# AVR128DB48_Curiosity_Nano_Debugger.net
KiCad netlist of a schematic drawn in Altium Designer
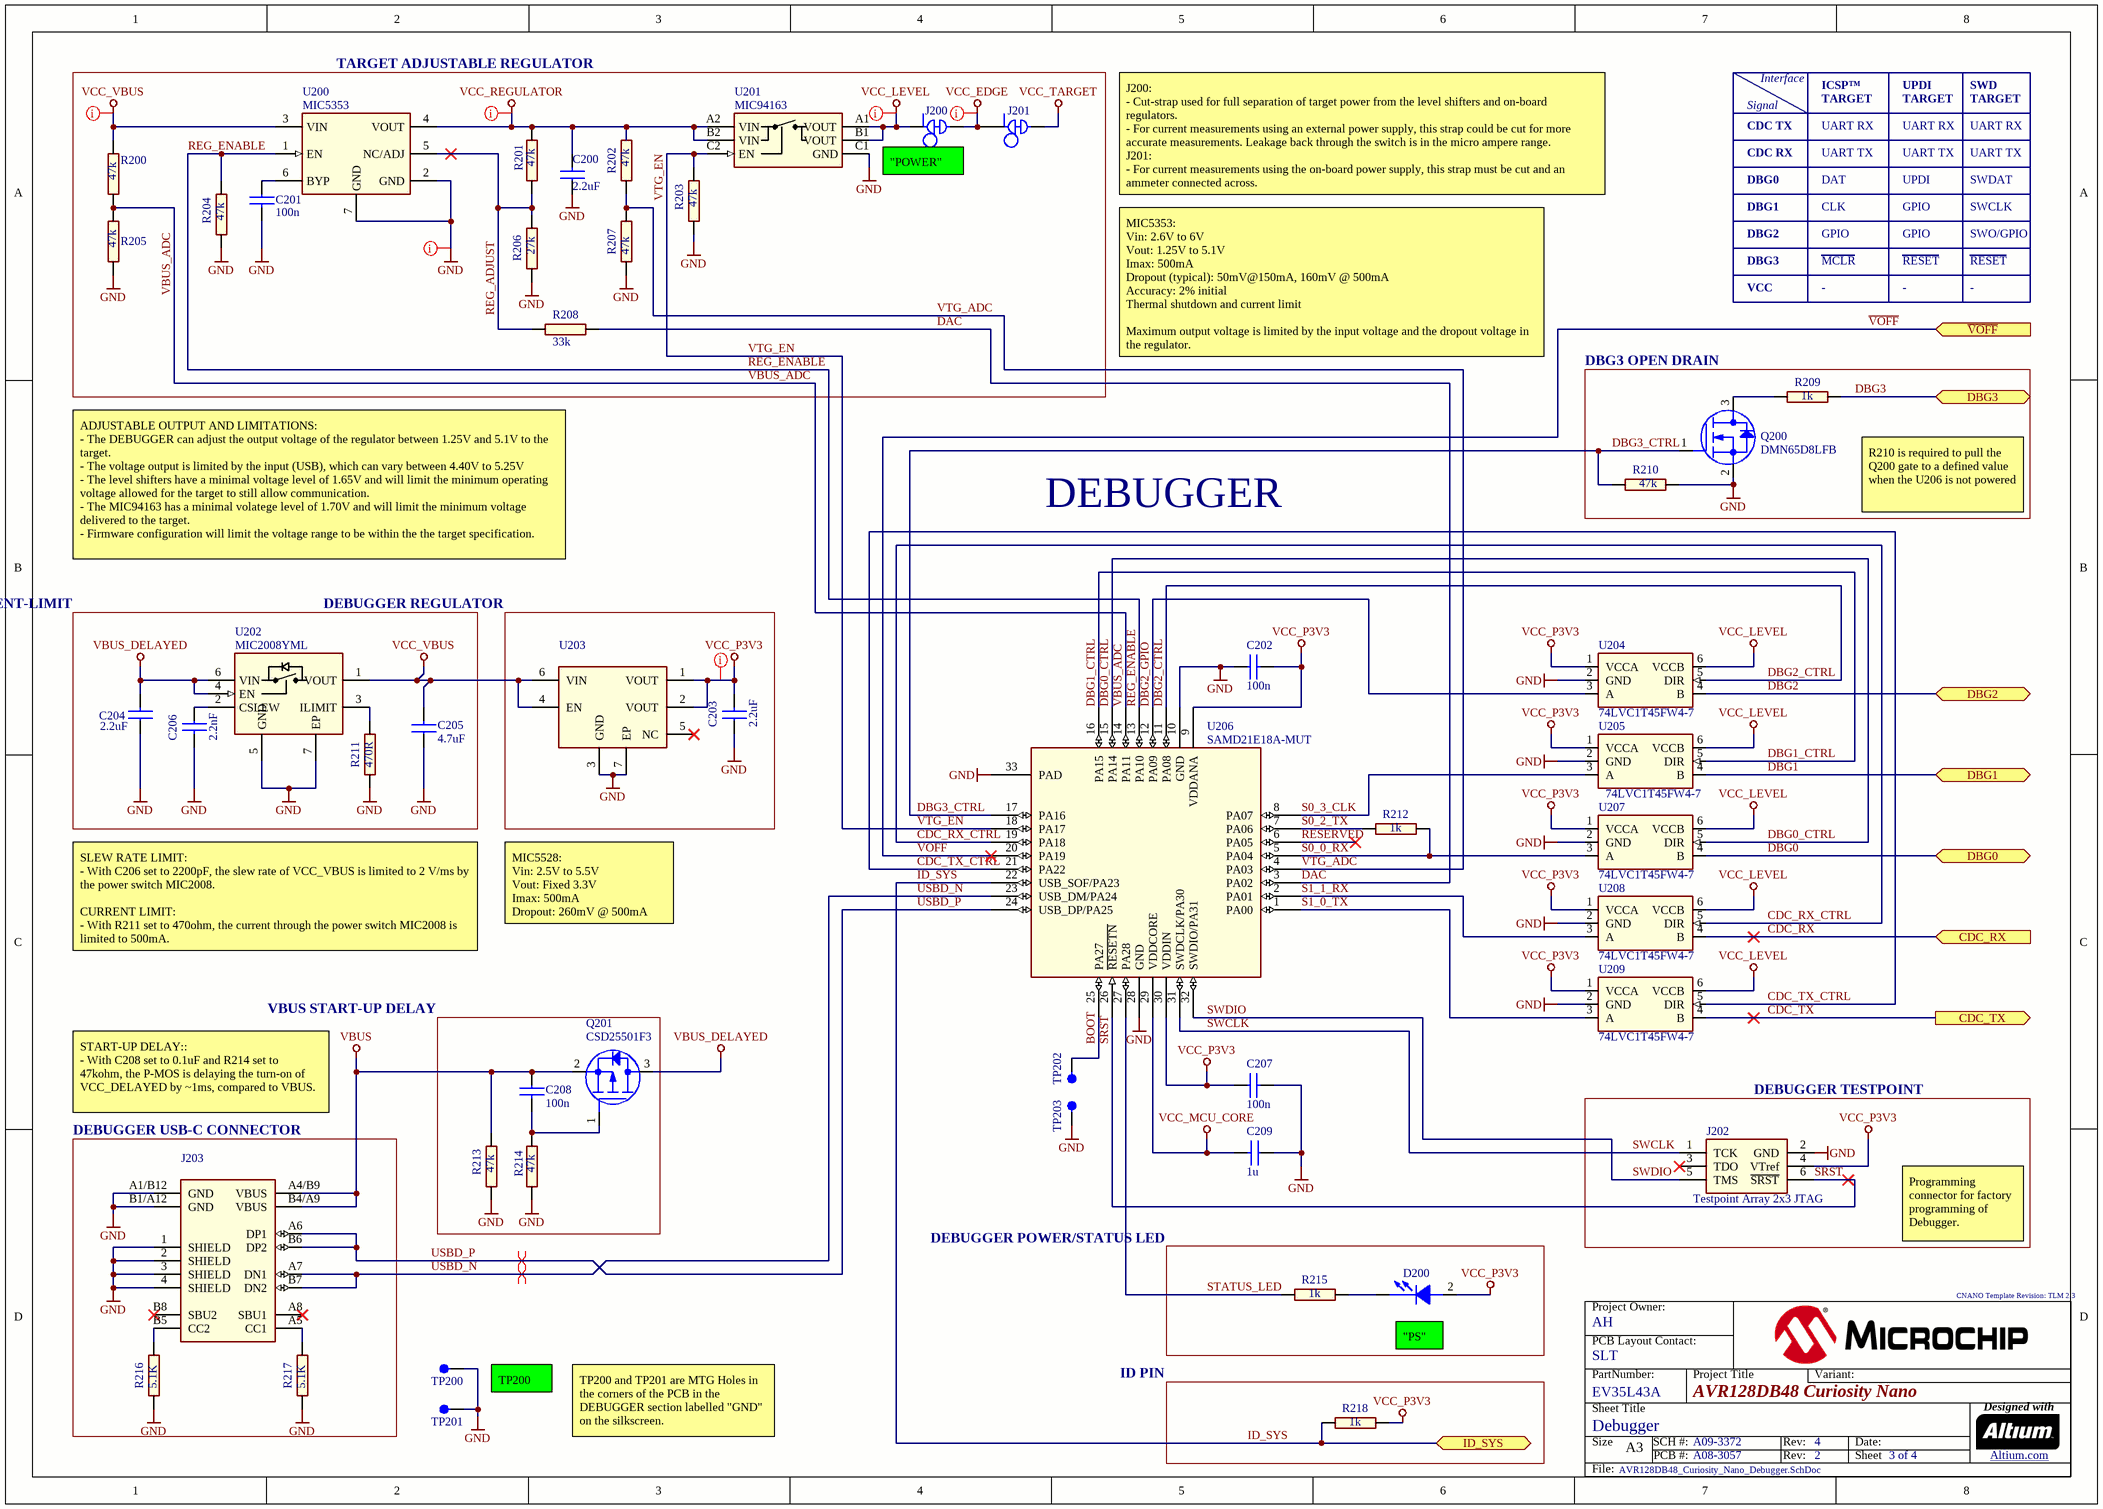
[diagram p0: AVR128DB48_Curiosity_Nano_Debugger.SchDoc]

(export (version "E")
  (design (tool "Eeschema 10.0.6"))
  (components
    (comp (ref "C200")
      (value "2.2uF")
      (footprint "AP1-00148")
      (description "CAP CER 2.2UF 10V 10% X5R 0402")
      (fields (field (name "TOLERANCE") "+/-10%") (field (name "MANUFACTURER") "TDK"))
      (libsource (lib "AltiumDbLib") (part "CAP-NONPOL"))
    )
    (comp (ref "C201")
      (value "100n")
      (footprint "AP1-00148")
      (description "Ceramic capacitor, SMD 0402, X7R, 16V, +/-10%")
      (fields (field (name "TOLERANCE") "16V, +/-10%") (field (name "MANUFACTURER") "Yageo"))
      (libsource (lib "AltiumDbLib") (part "CAP-NONPOL"))
    )
    (comp (ref "C202")
      (value "100n")
      (footprint "AP1-00148")
      (description "Ceramic capacitor, SMD 0402, X7R, 16V, +/-10%")
      (fields (field (name "TOLERANCE") "16V, +/-10%") (field (name "MANUFACTURER") "Yageo"))
      (libsource (lib "AltiumDbLib") (part "CAP-NONPOL"))
    )
    (comp (ref "C203")
      (value "2.2uF")
      (footprint "AP1-00148")
      (description "CAP CER 2.2UF 10V 10% X5R 0402")
      (fields (field (name "TOLERANCE") "+/-10%") (field (name "MANUFACTURER") "TDK"))
      (libsource (lib "AltiumDbLib") (part "CAP-NONPOL"))
    )
    (comp (ref "C204")
      (value "2.2uF")
      (footprint "AP1-00148")
      (description "CAP CER 2.2UF 10V 10% X5R 0402")
      (fields (field (name "TOLERANCE") "+/-10%") (field (name "MANUFACTURER") "TDK"))
      (libsource (lib "AltiumDbLib") (part "CAP-NONPOL"))
    )
    (comp (ref "C205")
      (value "4.7uF")
      (footprint "AP1-00039")
      (description "Ceramic capacitor, SMD 0603, X5R, 10V, 10% (de31036)")
      (fields (field (name "TOLERANCE") "10%") (field (name "MANUFACTURER") "Yageo"))
      (libsource (lib "AltiumDbLib") (part "CAP-NONPOL"))
    )
    (comp (ref "C206")
      (value "2.2nF")
      (footprint "AP1-00148")
      (description "Ceramic capacitor, SMD 0402, C0G, 25V, +/-5%")
      (fields (field (name "TOLERANCE") "25V, +/-5%") (field (name "MANUFACTURER") "Kemet"))
      (libsource (lib "AltiumDbLib") (part "CAP-NONPOL"))
    )
    (comp (ref "C207")
      (value "100n")
      (footprint "AP1-00148")
      (description "Ceramic capacitor, SMD 0402, X7R, 16V, +/-10%")
      (fields (field (name "TOLERANCE") "16V, +/-10%") (field (name "MANUFACTURER") "Yageo"))
      (libsource (lib "AltiumDbLib") (part "CAP-NONPOL"))
    )
    (comp (ref "C208")
      (value "100n")
      (footprint "AP1-00148")
      (description "Ceramic capacitor, SMD 0402, X7R, 16V, +/-10%")
      (fields (field (name "TOLERANCE") "16V, +/-10%") (field (name "MANUFACTURER") "Yageo"))
      (libsource (lib "AltiumDbLib") (part "CAP-NONPOL"))
    )
    (comp (ref "C209")
      (value "1u")
      (footprint "AP1-00148")
      (description "Ceramic capacitor, SMD 0402, X5R, 6.3V, +/-10% (de26942)")
      (fields (field (name "TOLERANCE") "+/-10%") (field (name "MANUFACTURER") "Kemet"))
      (libsource (lib "AltiumDbLib") (part "CAP-NONPOL"))
    )
    (comp (ref "D200")
      (value "~")
      (footprint "AP4-00160")
      (description "LED, SMD 0402, Green, Wave length=569nm, 2.1mcd @ (1mA, 1.9Vf)rohm")
      (fields (field (name "MANUFACTURER") "ROHM") (field (name "MPN") "SML-P12MTT86R"))
      (libsource (lib "AltiumDbLib") (part "LED_12"))
    )
    (comp (ref "J200")
      (value "~")
      (footprint "AP8-00595")
      (description "Closed Link 0402")
      (libsource (lib "AltiumDbLib") (part "SMD-STRAP_CLOSED"))
    )
    (comp (ref "J201")
      (value "~")
      (footprint "AP8-01183")
      (description "Closed Link with w/hole for 1x2 100mil header")
      (libsource (lib "AltiumDbLib") (part "SMD-STRAP_CLOSED"))
    )
    (comp (ref "J202")
      (value "Testpoint Array 2x3 JTAG")
      (footprint "AP8-01249")
      (description "6-pin Testpoint Array, 0.8mm Pad, 1.27mm Pitch")
      (libsource (lib "AltiumDbLib") (part "TESTPOINT ARRAY 2x3 JTAG"))
    )
    (comp (ref "J203")
      (value "~")
      (footprint "AP8-01248")
      (description "USB2.0 Type-C, Surface mount signals and DIP shield")
      (fields (field (name "MANUFACTURER") "Cabcon A/S") (field (name "MPN") "L-KLS1-5409-R"))
      (libsource (lib "AltiumDbLib") (part "USB2.0-C_KLS1-5409"))
    )
    (comp (ref "Q200")
      (value "DMN65D8LFB")
      (footprint "AP5-00056")
      (description "N-channel MOSFET, DFN1006-3 (SOT883), 60V, 330mA, 4Ohm")
      (fields (field (name "MANUFACTURER") "Diodes Incorporated") (field (name "MPN") "DMN65D8LFB-7"))
      (libsource (lib "AltiumDbLib") (part "MOSFET_N_GSD"))
    )
    (comp (ref "Q201")
      (value "CSD25501F3")
      (footprint "AP5-00062")
      (description "P-Channel MOSFET, LGA, 20V, 3.6A, 76mOhm")
      (fields (field (name "MANUFACTURER") "Texas Instruments"))
      (libsource (lib "AltiumDbLib") (part "MOSFET_P_GSD"))
    )
    (comp (ref "R200")
      (value "47k")
      (footprint "AP2-00108")
      (description "Thick film resistor, SMD 0402, 1/16W, 1%")
      (fields (field (name "TOLERANCE") "1 %") (field (name "MANUFACTURER") "KOA"))
      (libsource (lib "AltiumDbLib") (part "R2"))
    )
    (comp (ref "R201")
      (value "47k")
      (footprint "AP2-00108")
      (description "Thick film resistor, SMD 0402, 1/16W, 1%")
      (fields (field (name "TOLERANCE") "1 %") (field (name "MANUFACTURER") "KOA"))
      (libsource (lib "AltiumDbLib") (part "R2"))
    )
    (comp (ref "R202")
      (value "47k")
      (footprint "AP2-00108")
      (description "Thick film resistor, SMD 0402, 1/16W, 1%")
      (fields (field (name "TOLERANCE") "1 %") (field (name "MANUFACTURER") "KOA"))
      (libsource (lib "") (part "R2_2"))
    )
    (comp (ref "R203")
      (value "47k")
      (footprint "AP2-00108")
      (description "Thick film resistor, SMD 0402, 1/16W, 1%")
      (fields (field (name "TOLERANCE") "1 %") (field (name "MANUFACTURER") "KOA"))
      (libsource (lib "AltiumDbLib") (part "R2"))
    )
    (comp (ref "R204")
      (value "47k")
      (footprint "AP2-00108")
      (description "Thick film resistor, SMD 0402, 1/16W, 1%")
      (fields (field (name "TOLERANCE") "1 %") (field (name "MANUFACTURER") "KOA"))
      (libsource (lib "AltiumDbLib") (part "R2"))
    )
    (comp (ref "R205")
      (value "47k")
      (footprint "AP2-00108")
      (description "Thick film resistor, SMD 0402, 1/16W, 1%")
      (fields (field (name "TOLERANCE") "1 %") (field (name "MANUFACTURER") "KOA"))
      (libsource (lib "") (part "R2_2"))
    )
    (comp (ref "R206")
      (value "27k")
      (footprint "AP2-00108")
      (description "Thick film resistor, SMD 0402, 1/16W, 1%")
      (fields (field (name "TOLERANCE") "1 %") (field (name "MANUFACTURER") "Yageo"))
      (libsource (lib "") (part "R2_2"))
    )
    (comp (ref "R207")
      (value "47k")
      (footprint "AP2-00108")
      (description "Thick film resistor, SMD 0402, 1/16W, 1%")
      (fields (field (name "TOLERANCE") "1 %") (field (name "MANUFACTURER") "KOA"))
      (libsource (lib "") (part "R2_2"))
    )
    (comp (ref "R208")
      (value "33k")
      (footprint "AP2-00108")
      (description "Thick film resistor, SMD 0402, 1/16W, 1%")
      (fields (field (name "TOLERANCE") "1 %") (field (name "MANUFACTURER") "Yageo"))
      (libsource (lib "") (part "R2_1"))
    )
    (comp (ref "R209")
      (value "1k")
      (footprint "AP2-00108")
      (description "Thick film resistor, SMD 0402, 1/16W, 1%")
      (fields (field (name "TOLERANCE") "1 %") (field (name "MANUFACTURER") "Yageo"))
      (libsource (lib "") (part "R2_2"))
    )
    (comp (ref "R210")
      (value "47k")
      (footprint "AP2-00108")
      (description "Thick film resistor, SMD 0402, 1/16W, 1%")
      (fields (field (name "TOLERANCE") "1 %") (field (name "MANUFACTURER") "KOA"))
      (libsource (lib "") (part "R2_2"))
    )
    (comp (ref "R211")
      (value "470R")
      (footprint "AP2-00108")
      (description "Thick film resistror, SMD 0402, 1/16W, 1%")
      (fields (field (name "TOLERANCE") "1%") (field (name "MANUFACTURER") "Yageo"))
      (libsource (lib "AltiumDbLib") (part "R2"))
    )
    (comp (ref "R212")
      (value "1k")
      (footprint "AP2-00108")
      (description "Thick film resistor, SMD 0402, 1/16W, 1%")
      (fields (field (name "TOLERANCE") "1 %") (field (name "MANUFACTURER") "Yageo"))
      (libsource (lib "") (part "R2_3"))
    )
    (comp (ref "R213")
      (value "47k")
      (footprint "AP2-00108")
      (description "Thick film resistor, SMD 0402, 1/16W, 1%")
      (fields (field (name "TOLERANCE") "1 %") (field (name "MANUFACTURER") "KOA"))
      (libsource (lib "AltiumDbLib") (part "R2"))
    )
    (comp (ref "R214")
      (value "47k")
      (footprint "AP2-00108")
      (description "Thick film resistor, SMD 0402, 1/16W, 1%")
      (fields (field (name "TOLERANCE") "1 %") (field (name "MANUFACTURER") "KOA"))
      (libsource (lib "AltiumDbLib") (part "R2"))
    )
    (comp (ref "R215")
      (value "1k")
      (footprint "AP2-00108")
      (description "Thick film resistor, SMD 0402, 1/16W, 1%")
      (fields (field (name "TOLERANCE") "1 %") (field (name "MANUFACTURER") "Yageo"))
      (libsource (lib "") (part "R2_3"))
    )
    (comp (ref "R216")
      (value "5.1K")
      (footprint "AP2-00108")
      (description "Thick film resistor, SMD 0402, 1/10W, 1%")
      (fields (field (name "TOLERANCE") "1%") (field (name "MANUFACTURER") "Panasonic"))
      (libsource (lib "AltiumDbLib") (part "R2"))
    )
    (comp (ref "R217")
      (value "5.1K")
      (footprint "AP2-00108")
      (description "Thick film resistor, SMD 0402, 1/10W, 1%")
      (fields (field (name "TOLERANCE") "1%") (field (name "MANUFACTURER") "Panasonic"))
      (libsource (lib "AltiumDbLib") (part "R2"))
    )
    (comp (ref "R218")
      (value "1k")
      (footprint "AP2-00108")
      (description "Thick film resistor, SMD 0402, 1/16W, 1%")
      (fields (field (name "TOLERANCE") "1 %") (field (name "MANUFACTURER") "Yageo"))
      (libsource (lib "") (part "R2_1"))
    )
    (comp (ref "TP200")
      (value "PCB implemented component.")
      (footprint "AP8-01250")
      (description "TH Test point - D3.6H2.7")
      (libsource (lib "AltiumDbLib") (part "TESTPOINT"))
    )
    (comp (ref "TP201")
      (value "PCB implemented component.")
      (footprint "AP8-01250")
      (description "TH Test point - D3.6H2.7")
      (libsource (lib "AltiumDbLib") (part "TESTPOINT"))
    )
    (comp (ref "TP202")
      (value "PCB implemented component.")
      (footprint "AP8-00870")
      (description "SMD Test point - 0.8mm")
      (libsource (lib "AltiumDbLib") (part "TESTPOINT"))
    )
    (comp (ref "TP203")
      (value "PCB implemented component.")
      (footprint "AP8-00870")
      (description "SMD Test point - 0.8mm")
      (libsource (lib "AltiumDbLib") (part "TESTPOINT"))
    )
    (comp (ref "U200")
      (value "MIC5353")
      (footprint "AP6-00504")
      (description "500mA Ultra Low Dropout LDO regulator, 2% accuracy, 1.6x1.6mm MLF")
      (fields (field (name "MANUFACTURER") "Microchip") (field (name "MPN") "MIC5353YMT-TR"))
      (libsource (lib "AltiumDbLib") (part "MIC5319"))
    )
    (comp (ref "U201")
      (value "MIC94163")
      (footprint "AP6-00513")
      (description "Loadswitch, Rds(on) = 14.5mohm, 1.0mm x 1.5mm WLCSP, reverse blocking")
      (fields (field (name "MANUFACTURER") "Microchip") (field (name "MPN") "MIC94163YCS-TR"))
      (libsource (lib "AltiumDbLib") (part "MIC94163"))
    )
    (comp (ref "U202")
      (value "MIC2008YML")
      (footprint "AP6-00576")
      (description "0.2A- 2.5A adjustable current limit power switch, 2mm x 2mm DFN")
      (fields (field (name "MANUFACTURER") "Microchip") (field (name "MPN") "MIC2008YML-TR"))
      (libsource (lib "AltiumDbLib") (part "MIC2008YML-TR VDFN-6"))
    )
    (comp (ref "U203")
      (value "~")
      (footprint "AP6-00481")
      (description "LDO 3.3V 0.5A 6TDFN")
      (fields (field (name "MANUFACTURER") "Microchip") (field (name "MPN") "MIC5528-3.3YMT-T5"))
      (libsource (lib "AltiumDbLib") (part "MIC5528"))
    )
    (comp (ref "U204")
      (value "74LVC1T45FW4-7")
      (footprint "AP6-00575")
      (description "Single-Bit Dual-Supply Transceive, 1.65-5.5 Translation and 3-State Outputs")
      (fields (field (name "MANUFACTURER") "Diodes Incorporated"))
      (libsource (lib "AltiumDbLib") (part "SN74LVC1T45DCKR"))
    )
    (comp (ref "U205")
      (value "74LVC1T45FW4-7")
      (footprint "AP6-00575")
      (description "Single-Bit Dual-Supply Transceive, 1.65-5.5 Translation and 3-State Outputs")
      (fields (field (name "MANUFACTURER") "Diodes Incorporated"))
      (libsource (lib "AltiumDbLib") (part "SN74LVC1T45DCKR"))
    )
    (comp (ref "U206")
      (value "SAMD21E18A-MUT")
      (footprint "AP6-00418")
      (description "32-bit RISC MCU 32pin")
      (fields (field (name "MANUFACTURER") "Microchip") (field (name "MPN") "ATSAMD21E18A-MUT"))
      (libsource (lib "AltiumDbLib") (part "SAMD21E_QFN32"))
    )
    (comp (ref "U207")
      (value "74LVC1T45FW4-7")
      (footprint "AP6-00575")
      (description "Single-Bit Dual-Supply Transceive, 1.65-5.5 Translation and 3-State Outputs")
      (fields (field (name "MANUFACTURER") "Diodes Incorporated"))
      (libsource (lib "AltiumDbLib") (part "SN74LVC1T45DCKR"))
    )
    (comp (ref "U208")
      (value "74LVC1T45FW4-7")
      (footprint "AP6-00575")
      (description "Single-Bit Dual-Supply Transceive, 1.65-5.5 Translation and 3-State Outputs")
      (fields (field (name "MANUFACTURER") "Diodes Incorporated"))
      (libsource (lib "AltiumDbLib") (part "SN74LVC1T45DCKR"))
    )
    (comp (ref "U209")
      (value "74LVC1T45FW4-7")
      (footprint "AP6-00575")
      (description "Single-Bit Dual-Supply Transceive, 1.65-5.5 Translation and 3-State Outputs")
      (fields (field (name "MANUFACTURER") "Diodes Incorporated"))
      (libsource (lib "AltiumDbLib") (part "SN74LVC1T45DCKR"))
    )
  )
  (nets
    (net (code "1") (name "/BOOT") (class "Default")
      (node (ref "TP202") (pin "1") (pinfunction "1_1") (pintype "passive"))
      (node (ref "U206") (pin "25") (pinfunction "PA27_25") (pintype "bidirectional"))
    )
    (net (code "2") (name "/CDC_RX") (class "Default")
      (node (ref "U208") (pin "4") (pinfunction "B_4") (pintype "bidirectional"))
    )
    (net (code "3") (name "/CDC_RX_CTRL") (class "Default")
      (node (ref "U206") (pin "19") (pinfunction "PA18_19") (pintype "bidirectional"))
      (node (ref "U208") (pin "5") (pinfunction "DIR_5") (pintype "input"))
    )
    (net (code "4") (name "/CDC_TX") (class "Default")
      (node (ref "U209") (pin "4") (pinfunction "B_4") (pintype "bidirectional"))
    )
    (net (code "5") (name "/CDC_TX_CTRL") (class "Default")
      (node (ref "U206") (pin "21") (pinfunction "PA22_21") (pintype "bidirectional"))
      (node (ref "U209") (pin "5") (pinfunction "DIR_5") (pintype "input"))
    )
    (net (code "6") (name "/DAC") (class "Default")
      (node (ref "R208") (pin "2") (pinfunction "2_2") (pintype "passive"))
      (node (ref "U206") (pin "3") (pinfunction "PA02_3") (pintype "bidirectional"))
    )
    (net (code "7") (name "/DBG0") (class "Default")
      (node (ref "U207") (pin "4") (pinfunction "B_4") (pintype "bidirectional"))
    )
    (net (code "8") (name "/DBG0_CTRL") (class "Default")
      (node (ref "U206") (pin "15") (pinfunction "PA14_15") (pintype "bidirectional"))
      (node (ref "U207") (pin "5") (pinfunction "DIR_5") (pintype "input"))
    )
    (net (code "9") (name "/DBG1") (class "Default")
      (node (ref "U205") (pin "4") (pinfunction "B_4") (pintype "bidirectional"))
    )
    (net (code "10") (name "/DBG1_CTRL") (class "Default")
      (node (ref "U205") (pin "5") (pinfunction "DIR_5") (pintype "input"))
      (node (ref "U206") (pin "16") (pinfunction "PA15_16") (pintype "bidirectional"))
    )
    (net (code "11") (name "/DBG2") (class "Default")
      (node (ref "U204") (pin "4") (pinfunction "B_4") (pintype "bidirectional"))
    )
    (net (code "12") (name "/DBG2_CTRL") (class "Default")
      (node (ref "U204") (pin "5") (pinfunction "DIR_5") (pintype "input"))
      (node (ref "U206") (pin "11") (pinfunction "PA08_11") (pintype "bidirectional"))
    )
    (net (code "13") (name "/DBG2_GPIO") (class "Default")
      (node (ref "U204") (pin "3") (pinfunction "A_3") (pintype "bidirectional"))
      (node (ref "U206") (pin "12") (pinfunction "PA09_12") (pintype "bidirectional"))
    )
    (net (code "14") (name "/DBG3") (class "Default")
      (node (ref "R209") (pin "2") (pinfunction "2_2") (pintype "passive"))
    )
    (net (code "15") (name "/DBG3_CTRL") (class "Default")
      (node (ref "Q200") (pin "1") (pinfunction "G_1") (pintype "passive"))
      (node (ref "R210") (pin "1") (pinfunction "1_1") (pintype "passive"))
      (node (ref "U206") (pin "17") (pinfunction "PA16_17") (pintype "bidirectional"))
    )
    (net (code "16") (name "/ID_SYS") (class "Default")
      (node (ref "R218") (pin "1") (pinfunction "1_1") (pintype "passive"))
      (node (ref "U206") (pin "22") (pinfunction "USB_SOF/PA23_22") (pintype "bidirectional"))
    )
    (net (code "17") (name "/REG_ADJUST") (class "Default")
      (node (ref "R201") (pin "2") (pinfunction "2_2") (pintype "passive"))
      (node (ref "R206") (pin "2") (pinfunction "2_2") (pintype "passive"))
      (node (ref "R208") (pin "1") (pinfunction "1_1") (pintype "passive"))
      (node (ref "U200") (pin "5") (pinfunction "NC/ADJ_5") (pintype "passive"))
    )
    (net (code "18") (name "/REG_ENABLE") (class "Default")
      (node (ref "R204") (pin "1") (pinfunction "1_1") (pintype "passive"))
      (node (ref "U200") (pin "1") (pinfunction "EN_1") (pintype "input"))
      (node (ref "U206") (pin "13") (pinfunction "PA10_13") (pintype "bidirectional"))
    )
    (net (code "19") (name "/RESERVED") (class "Default")
      (node (ref "U206") (pin "6") (pinfunction "PA05_6") (pintype "bidirectional+no_connect"))
    )
    (net (code "20") (name "/S0_0_RX") (class "Default")
      (node (ref "R212") (pin "1") (pinfunction "1_1") (pintype "passive"))
      (node (ref "U206") (pin "5") (pinfunction "PA04_5") (pintype "bidirectional"))
      (node (ref "U207") (pin "3") (pinfunction "A_3") (pintype "bidirectional"))
    )
    (net (code "21") (name "/S0_2_TX") (class "Default")
      (node (ref "R212") (pin "2") (pinfunction "2_2") (pintype "passive"))
      (node (ref "U206") (pin "7") (pinfunction "PA06_7") (pintype "bidirectional"))
    )
    (net (code "22") (name "/S0_3_CLK") (class "Default")
      (node (ref "U205") (pin "3") (pinfunction "A_3") (pintype "bidirectional"))
      (node (ref "U206") (pin "8") (pinfunction "PA07_8") (pintype "bidirectional"))
    )
    (net (code "23") (name "/S1_0_TX") (class "Default")
      (node (ref "U206") (pin "1") (pinfunction "PA00_1") (pintype "bidirectional"))
      (node (ref "U209") (pin "3") (pinfunction "A_3") (pintype "bidirectional"))
    )
    (net (code "24") (name "/S1_1_RX") (class "Default")
      (node (ref "U206") (pin "2") (pinfunction "PA01_2") (pintype "bidirectional"))
      (node (ref "U208") (pin "3") (pinfunction "A_3") (pintype "bidirectional"))
    )
    (net (code "25") (name "/STATUS_LED") (class "Default")
      (node (ref "R215") (pin "2") (pinfunction "2_2") (pintype "passive"))
      (node (ref "U206") (pin "27") (pinfunction "PA28_27") (pintype "bidirectional"))
    )
    (net (code "26") (name "/SWCLK") (class "Default")
      (node (ref "J202") (pin "1") (pinfunction "TCK_1") (pintype "passive"))
      (node (ref "U206") (pin "31") (pinfunction "SWDCLK/PA30_31") (pintype "bidirectional"))
    )
    (net (code "27") (name "/SWDIO") (class "Default")
      (node (ref "J202") (pin "5") (pinfunction "TMS_5") (pintype "passive"))
      (node (ref "U206") (pin "32") (pinfunction "SWDIO/PA31_32") (pintype "bidirectional"))
    )
    (net (code "28") (name "/USBD_N") (class "Default")
      (node (ref "J203") (pin "A7") (pinfunction "DN1_A7") (pintype "bidirectional"))
      (node (ref "J203") (pin "B7") (pinfunction "DN2_B7") (pintype "bidirectional"))
      (node (ref "U206") (pin "23") (pinfunction "USB_DM/PA24_23") (pintype "bidirectional"))
    )
    (net (code "29") (name "/USBD_P") (class "Default")
      (node (ref "J203") (pin "A6") (pinfunction "DP1_A6") (pintype "bidirectional"))
      (node (ref "J203") (pin "B6") (pinfunction "DP2_B6") (pintype "bidirectional"))
      (node (ref "U206") (pin "24") (pinfunction "USB_DP/PA25_24") (pintype "bidirectional"))
    )
    (net (code "30") (name "/VBUS_ADC") (class "Default")
      (node (ref "R200") (pin "2") (pinfunction "2_2") (pintype "passive"))
      (node (ref "R205") (pin "2") (pinfunction "2_2") (pintype "passive"))
      (node (ref "U206") (pin "14") (pinfunction "PA11_14") (pintype "bidirectional"))
    )
    (net (code "31") (name "/VTG_ADC") (class "Default")
      (node (ref "R202") (pin "1") (pinfunction "1_1") (pintype "passive"))
      (node (ref "R207") (pin "2") (pinfunction "2_2") (pintype "passive"))
      (node (ref "U206") (pin "4") (pinfunction "PA03_4") (pintype "bidirectional"))
    )
    (net (code "32") (name "/VTG_EN") (class "Default")
      (node (ref "R203") (pin "1") (pinfunction "1_1") (pintype "passive"))
      (node (ref "U201") (pin "C2") (pinfunction "EN_C2") (pintype "input"))
      (node (ref "U206") (pin "18") (pinfunction "PA17_18") (pintype "bidirectional"))
    )
    (net (code "33") (name "/~{SRST}") (class "Default")
      (node (ref "J202") (pin "6") (pinfunction "~{SRST}_6") (pintype "passive"))
      (node (ref "U206") (pin "26") (pinfunction "~{RESETN}_26") (pintype "input"))
    )
    (net (code "34") (name "/~{VOFF}") (class "Default")
      (node (ref "U206") (pin "20") (pinfunction "PA19_20") (pintype "bidirectional+no_connect"))
    )
    (net (code "35") (name "GND") (class "Default")
      (node (ref "C200") (pin "1") (pinfunction "1_1") (pintype "passive"))
      (node (ref "C201") (pin "2") (pinfunction "2_2") (pintype "passive"))
      (node (ref "C202") (pin "1") (pinfunction "1_1") (pintype "passive"))
      (node (ref "C203") (pin "1") (pinfunction "1_1") (pintype "passive"))
      (node (ref "C204") (pin "1") (pinfunction "1_1") (pintype "passive"))
      (node (ref "C205") (pin "1") (pinfunction "1_1") (pintype "passive"))
      (node (ref "C206") (pin "2") (pinfunction "2_2") (pintype "passive"))
      (node (ref "C207") (pin "2") (pinfunction "2_2") (pintype "passive"))
      (node (ref "C209") (pin "1") (pinfunction "1_1") (pintype "passive"))
      (node (ref "J202") (pin "2") (pinfunction "GND_2") (pintype "power_in"))
      (node (ref "J203") (pin "1") (pinfunction "SHIELD_1") (pintype "passive"))
      (node (ref "J203") (pin "2") (pinfunction "SHIELD_2") (pintype "passive"))
      (node (ref "J203") (pin "3") (pinfunction "SHIELD_3") (pintype "passive"))
      (node (ref "J203") (pin "4") (pinfunction "SHIELD_4") (pintype "passive"))
      (node (ref "J203") (pin "A1/B12") (pinfunction "GND_A1/B12") (pintype "power_in"))
      (node (ref "J203") (pin "B1/A12") (pinfunction "GND_B1/A12") (pintype "power_in"))
      (node (ref "Q200") (pin "2") (pinfunction "S_2") (pintype "passive"))
      (node (ref "R203") (pin "2") (pinfunction "2_2") (pintype "passive"))
      (node (ref "R204") (pin "2") (pinfunction "2_2") (pintype "passive"))
      (node (ref "R205") (pin "1") (pinfunction "1_1") (pintype "passive"))
      (node (ref "R206") (pin "1") (pinfunction "1_1") (pintype "passive"))
      (node (ref "R207") (pin "1") (pinfunction "1_1") (pintype "passive"))
      (node (ref "R210") (pin "2") (pinfunction "2_2") (pintype "passive"))
      (node (ref "R211") (pin "2") (pinfunction "2_2") (pintype "passive"))
      (node (ref "R213") (pin "2") (pinfunction "2_2") (pintype "passive"))
      (node (ref "R214") (pin "2") (pinfunction "2_2") (pintype "passive"))
      (node (ref "R216") (pin "2") (pinfunction "2_2") (pintype "passive"))
      (node (ref "R217") (pin "2") (pinfunction "2_2") (pintype "passive"))
      (node (ref "TP200") (pin "1") (pinfunction "1_1") (pintype "passive"))
      (node (ref "TP201") (pin "1") (pinfunction "1_1") (pintype "passive"))
      (node (ref "TP203") (pin "1") (pinfunction "1_1") (pintype "passive"))
      (node (ref "U200") (pin "2") (pinfunction "GND_2") (pintype "power_in"))
      (node (ref "U200") (pin "7") (pinfunction "GND_7") (pintype "power_in"))
      (node (ref "U201") (pin "C1") (pinfunction "GND_C1") (pintype "power_in"))
      (node (ref "U202") (pin "5") (pinfunction "GND_5") (pintype "power_in"))
      (node (ref "U202") (pin "7") (pinfunction "EP_7") (pintype "power_in"))
      (node (ref "U203") (pin "3") (pinfunction "GND_3") (pintype "passive"))
      (node (ref "U203") (pin "7") (pinfunction "EP_7") (pintype "passive"))
      (node (ref "U204") (pin "2") (pinfunction "GND_2") (pintype "power_in"))
      (node (ref "U205") (pin "2") (pinfunction "GND_2") (pintype "power_in"))
      (node (ref "U206") (pin "10") (pinfunction "GND_10") (pintype "power_in"))
      (node (ref "U206") (pin "28") (pinfunction "GND_28") (pintype "power_in"))
      (node (ref "U206") (pin "33") (pinfunction "PAD_33") (pintype "passive"))
      (node (ref "U207") (pin "2") (pinfunction "GND_2") (pintype "power_in"))
      (node (ref "U208") (pin "2") (pinfunction "GND_2") (pintype "power_in"))
      (node (ref "U209") (pin "2") (pinfunction "GND_2") (pintype "power_in"))
    )
    (net (code "36") (name "Net-(D200-CATHODE)") (class "Default")
      (node (ref "D200") (pin "1") (pinfunction "CATHODE_1") (pintype "passive"))
      (node (ref "R215") (pin "1") (pinfunction "1_1") (pintype "passive"))
    )
    (net (code "37") (name "Net-(J203-CC1)") (class "Default")
      (node (ref "J203") (pin "A5") (pinfunction "CC1_A5") (pintype "passive"))
      (node (ref "R217") (pin "1") (pinfunction "1_1") (pintype "passive"))
    )
    (net (code "38") (name "Net-(J203-CC2)") (class "Default")
      (node (ref "J203") (pin "B5") (pinfunction "CC2_B5") (pintype "passive"))
      (node (ref "R216") (pin "1") (pinfunction "1_1") (pintype "passive"))
    )
    (net (code "39") (name "Net-(Q200-D)") (class "Default")
      (node (ref "Q200") (pin "3") (pinfunction "D_3") (pintype "passive"))
      (node (ref "R209") (pin "1") (pinfunction "1_1") (pintype "passive"))
    )
    (net (code "40") (name "Net-(Q201-G)") (class "Default")
      (node (ref "C208") (pin "2") (pinfunction "2_2") (pintype "passive"))
      (node (ref "Q201") (pin "1") (pinfunction "G_1") (pintype "passive"))
      (node (ref "R214") (pin "1") (pinfunction "1_1") (pintype "passive"))
    )
    (net (code "41") (name "Net-(U200-BYP)") (class "Default")
      (node (ref "C201") (pin "1") (pinfunction "1_1") (pintype "passive"))
      (node (ref "U200") (pin "6") (pinfunction "BYP_6") (pintype "passive"))
    )
    (net (code "42") (name "Net-(U202-CSLEW)") (class "Default")
      (node (ref "C206") (pin "1") (pinfunction "1_1") (pintype "passive"))
      (node (ref "U202") (pin "2") (pinfunction "CSLEW_2") (pintype "passive"))
    )
    (net (code "43") (name "Net-(U202-ILIMIT)") (class "Default")
      (node (ref "R211") (pin "1") (pinfunction "1_1") (pintype "passive"))
      (node (ref "U202") (pin "3") (pinfunction "ILIMIT_3") (pintype "passive"))
    )
    (net (code "44") (name "VBUS") (class "Default")
      (node (ref "C208") (pin "1") (pinfunction "1_1") (pintype "passive"))
      (node (ref "J203") (pin "A4/B9") (pinfunction "VBUS_A4/B9") (pintype "power_in"))
      (node (ref "J203") (pin "B4/A9") (pinfunction "VBUS_B4/A9") (pintype "power_in"))
      (node (ref "Q201") (pin "2") (pinfunction "S_2") (pintype "passive"))
      (node (ref "R213") (pin "1") (pinfunction "1_1") (pintype "passive"))
    )
    (net (code "45") (name "VBUS_DELAYED") (class "Default")
      (node (ref "C204") (pin "2") (pinfunction "2_2") (pintype "passive"))
      (node (ref "Q201") (pin "3") (pinfunction "D_3") (pintype "passive"))
      (node (ref "U202") (pin "4") (pinfunction "EN_4") (pintype "input"))
      (node (ref "U202") (pin "6") (pinfunction "VIN_6") (pintype "power_in"))
    )
    (net (code "46") (name "VCC_EDGE") (class "Default")
      (node (ref "J200") (pin "2") (pinfunction "2_2") (pintype "passive"))
      (node (ref "J201") (pin "1") (pinfunction "1_1") (pintype "passive"))
    )
    (net (code "47") (name "VCC_LEVEL") (class "Default")
      (node (ref "J200") (pin "1") (pinfunction "1_1") (pintype "passive"))
      (node (ref "U201") (pin "A1") (pinfunction "VOUT_A1") (pintype "passive"))
      (node (ref "U201") (pin "B1") (pinfunction "VOUT_B1") (pintype "passive"))
      (node (ref "U204") (pin "6") (pinfunction "VCCB_6") (pintype "power_in"))
      (node (ref "U205") (pin "6") (pinfunction "VCCB_6") (pintype "power_in"))
      (node (ref "U207") (pin "6") (pinfunction "VCCB_6") (pintype "power_in"))
      (node (ref "U208") (pin "6") (pinfunction "VCCB_6") (pintype "power_in"))
      (node (ref "U209") (pin "6") (pinfunction "VCCB_6") (pintype "power_in"))
    )
    (net (code "48") (name "VCC_MCU_CORE") (class "Default")
      (node (ref "C209") (pin "2") (pinfunction "2_2") (pintype "passive"))
      (node (ref "U206") (pin "29") (pinfunction "VDDCORE_29") (pintype "power_in"))
    )
    (net (code "49") (name "VCC_P3V3") (class "Default")
      (node (ref "C202") (pin "2") (pinfunction "2_2") (pintype "passive"))
      (node (ref "C203") (pin "2") (pinfunction "2_2") (pintype "passive"))
      (node (ref "C207") (pin "1") (pinfunction "1_1") (pintype "passive"))
      (node (ref "D200") (pin "2") (pinfunction "ANODE_2") (pintype "passive"))
      (node (ref "J202") (pin "4") (pinfunction "VTref_4") (pintype "passive"))
      (node (ref "R218") (pin "2") (pinfunction "2_2") (pintype "passive"))
      (node (ref "U203") (pin "1") (pinfunction "VOUT_1") (pintype "power_in"))
      (node (ref "U203") (pin "2") (pinfunction "VOUT_2") (pintype "power_in"))
      (node (ref "U204") (pin "1") (pinfunction "VCCA_1") (pintype "power_in"))
      (node (ref "U205") (pin "1") (pinfunction "VCCA_1") (pintype "power_in"))
      (node (ref "U206") (pin "30") (pinfunction "VDDIN_30") (pintype "power_in"))
      (node (ref "U206") (pin "9") (pinfunction "VDDANA_9") (pintype "power_in"))
      (node (ref "U207") (pin "1") (pinfunction "VCCA_1") (pintype "power_in"))
      (node (ref "U208") (pin "1") (pinfunction "VCCA_1") (pintype "power_in"))
      (node (ref "U209") (pin "1") (pinfunction "VCCA_1") (pintype "power_in"))
    )
    (net (code "50") (name "VCC_REGULATOR") (class "Default")
      (node (ref "C200") (pin "2") (pinfunction "2_2") (pintype "passive"))
      (node (ref "R201") (pin "1") (pinfunction "1_1") (pintype "passive"))
      (node (ref "R202") (pin "2") (pinfunction "2_2") (pintype "passive"))
      (node (ref "U200") (pin "4") (pinfunction "VOUT_4") (pintype "power_in"))
      (node (ref "U201") (pin "A2") (pinfunction "VIN_A2") (pintype "passive"))
      (node (ref "U201") (pin "B2") (pinfunction "VIN_B2") (pintype "passive"))
    )
    (net (code "51") (name "VCC_TARGET") (class "Default")
      (node (ref "J201") (pin "2") (pinfunction "2_2") (pintype "passive"))
    )
    (net (code "52") (name "VCC_VBUS") (class "Default")
      (node (ref "C205") (pin "2") (pinfunction "2_2") (pintype "passive"))
      (node (ref "R200") (pin "1") (pinfunction "1_1") (pintype "passive"))
      (node (ref "U200") (pin "3") (pinfunction "VIN_3") (pintype "power_in"))
      (node (ref "U202") (pin "1") (pinfunction "VOUT_1") (pintype "power_in"))
      (node (ref "U203") (pin "4") (pinfunction "EN_4") (pintype "passive"))
      (node (ref "U203") (pin "6") (pinfunction "VIN_6") (pintype "power_in"))
    )
    (net (code "53") (name "unconnected-(J202-TDO-Pad3)") (class "Default")
      (node (ref "J202") (pin "3") (pinfunction "TDO_3") (pintype "passive+no_connect"))
    )
    (net (code "54") (name "unconnected-(J203-SBU1-PadA8)") (class "Default")
      (node (ref "J203") (pin "A8") (pinfunction "SBU1_A8") (pintype "passive+no_connect"))
    )
    (net (code "55") (name "unconnected-(J203-SBU2-PadB8)") (class "Default")
      (node (ref "J203") (pin "B8") (pinfunction "SBU2_B8") (pintype "passive+no_connect"))
    )
    (net (code "56") (name "unconnected-(U203-NC-Pad5)") (class "Default")
      (node (ref "U203") (pin "5") (pinfunction "NC_5") (pintype "passive+no_connect"))
    )
  )
)
